# input_output_buffers_DLFO.net
KiCad netlist of a schematic drawn in EAGLE
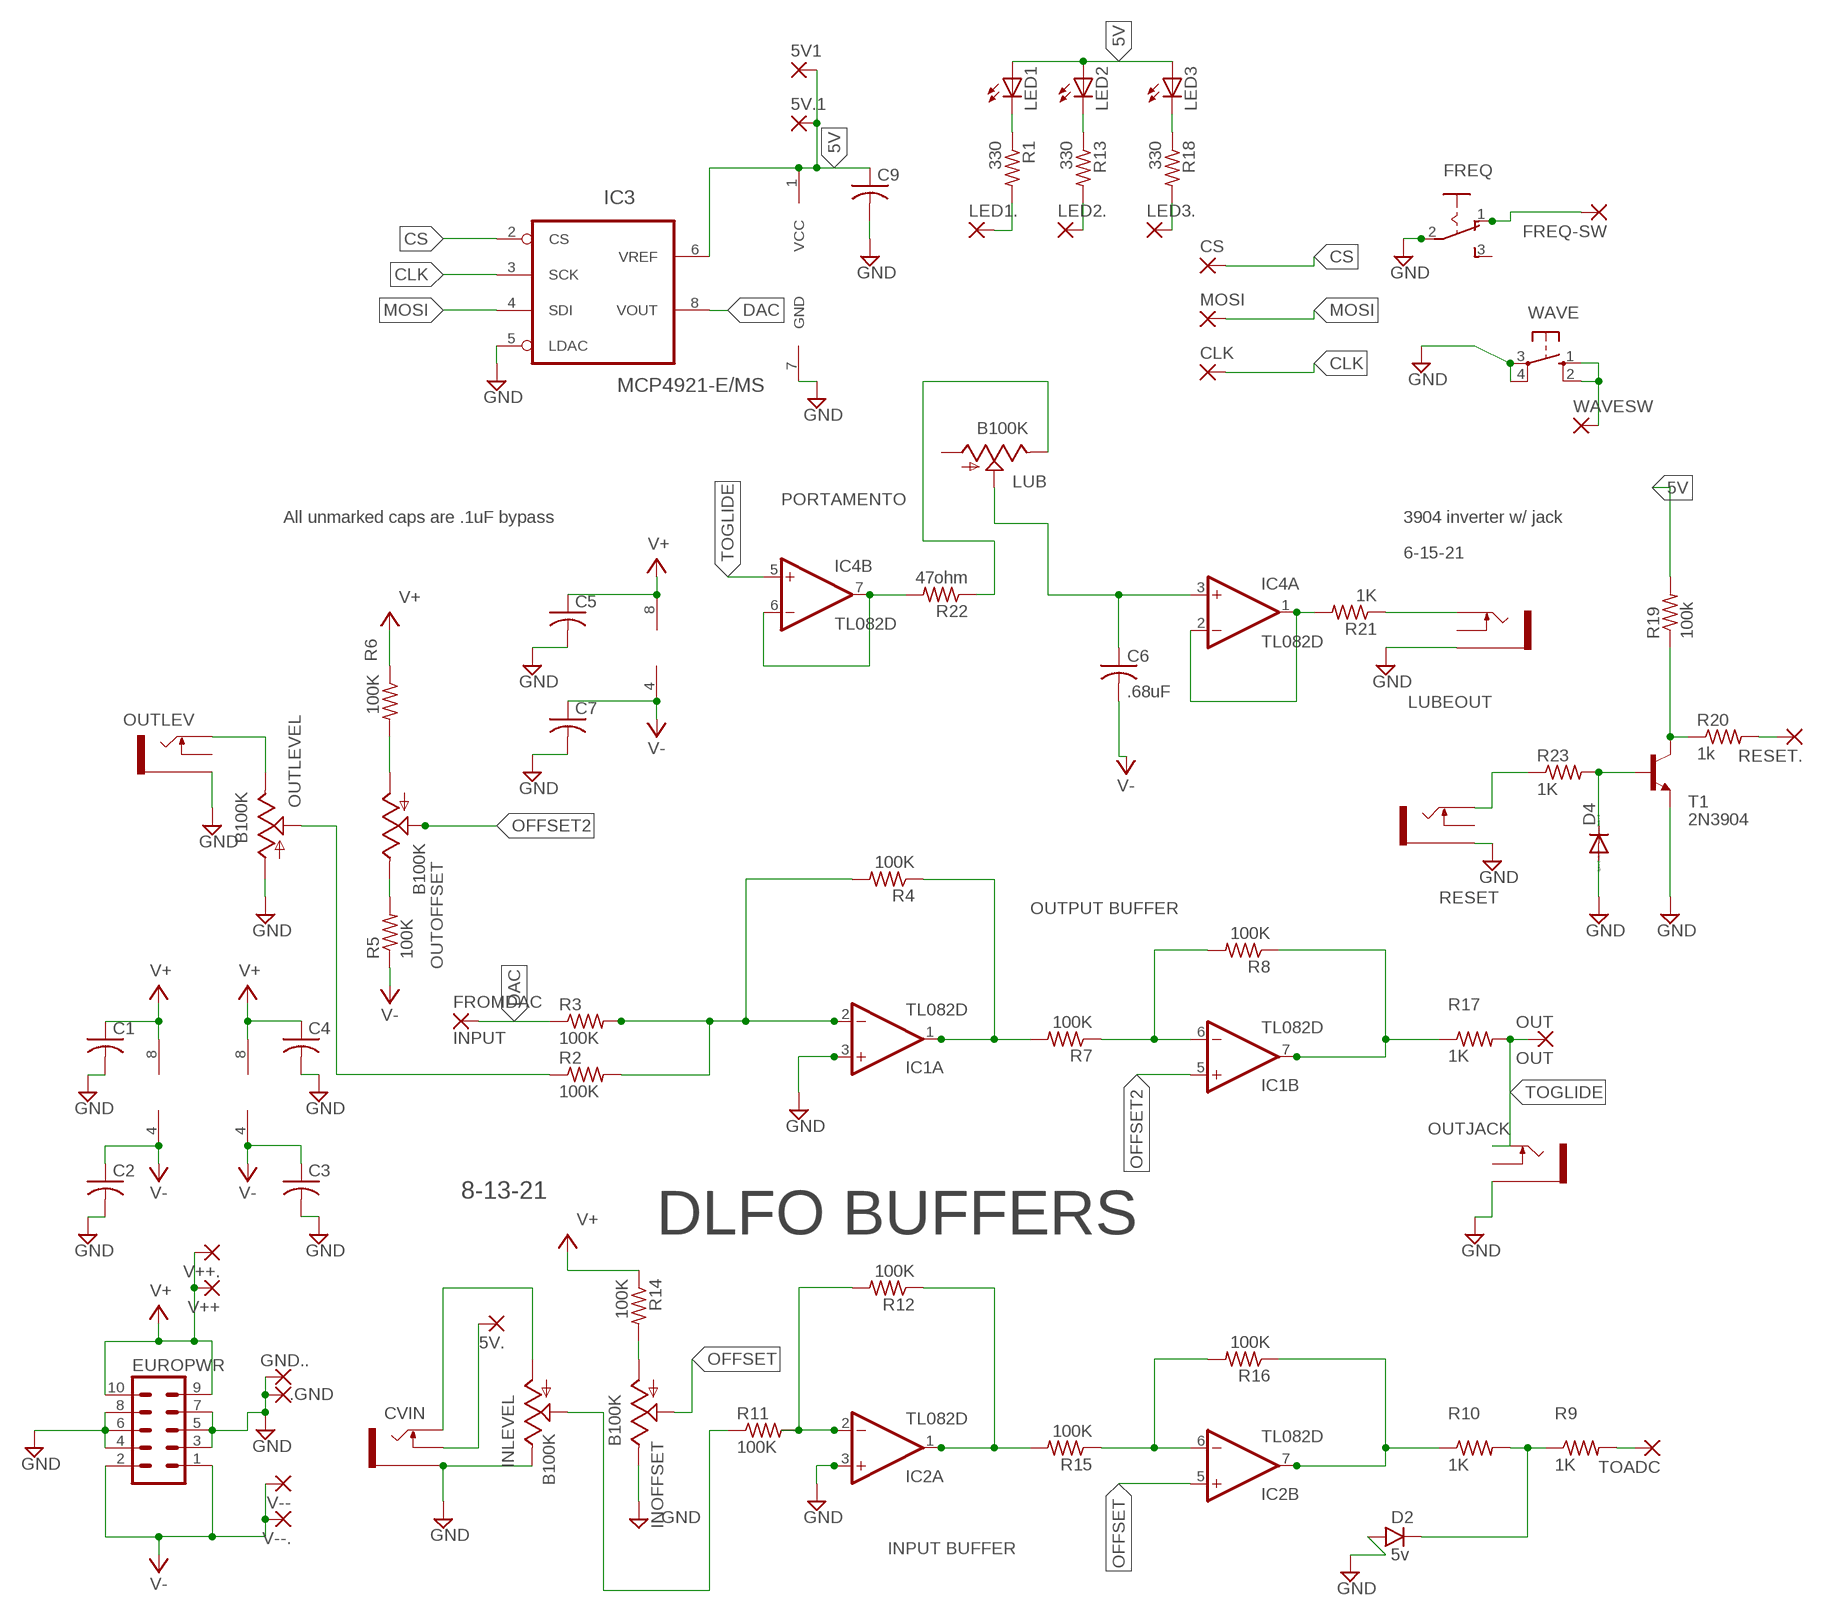
[diagram p0: schematic, sheet 1]

(export (version "E")
  (design (tool "Eeschema 10.0.6"))
  (components
    (comp (ref ".GND")
      (value "3,17/1,3")
      (footprint "eagle-import:3,17_1,3")
      (libsource (lib "eagle-import") (part "3,17/1,3"))
    )
    (comp (ref "5V.")
      (value "3,17/1,3")
      (footprint "eagle-import:3,17_1,3")
      (libsource (lib "eagle-import") (part "3,17/1,3"))
    )
    (comp (ref "5V.1")
      (value "WIREPAD2,54/1,0")
      (footprint "eagle-import:2,54_1,0")
      (libsource (lib "eagle-import") (part "WIREPAD2,54/1,0"))
    )
    (comp (ref "5V1")
      (value "WIREPAD2,54/1,0")
      (footprint "eagle-import:2,54_1,0")
      (libsource (lib "eagle-import") (part "WIREPAD2,54/1,0"))
    )
    (comp (ref "C1")
      (value "C-USC0603")
      (footprint "eagle-import:C0603")
      (libsource (lib "eagle-import") (part "C-USC0603"))
    )
    (comp (ref "C2")
      (value "C-USC0603")
      (footprint "eagle-import:C0603")
      (libsource (lib "eagle-import") (part "C-USC0603"))
    )
    (comp (ref "C3")
      (value "C-USC0603")
      (footprint "eagle-import:C0603")
      (libsource (lib "eagle-import") (part "C-USC0603"))
    )
    (comp (ref "C4")
      (value "C-USC0603")
      (footprint "eagle-import:C0603")
      (libsource (lib "eagle-import") (part "C-USC0603"))
    )
    (comp (ref "C5")
      (value "C-USC0603")
      (footprint "eagle-import:C0603")
      (libsource (lib "eagle-import") (part "C-USC0603"))
    )
    (comp (ref "C6")
      (value ".68uF")
      (footprint "eagle-import:C050-024X044")
      (libsource (lib "eagle-import") (part "C-US050-024X044"))
    )
    (comp (ref "C7")
      (value "C-USC0603")
      (footprint "eagle-import:C0603")
      (libsource (lib "eagle-import") (part "C-USC0603"))
    )
    (comp (ref "C9")
      (value "C-USC0603")
      (footprint "eagle-import:C0603")
      (libsource (lib "eagle-import") (part "C-USC0603"))
    )
    (comp (ref "CLK")
      (value "WIREPAD2,54/1,1")
      (footprint "eagle-import:2,54_1,1")
      (libsource (lib "eagle-import") (part "WIREPAD2,54/1,1"))
    )
    (comp (ref "CS")
      (value "WIREPAD2,54/1,0")
      (footprint "eagle-import:2,54_1,0")
      (libsource (lib "eagle-import") (part "WIREPAD2,54/1,0"))
    )
    (comp (ref "CVIN")
      (value "THONKICONNNEW")
      (footprint "eagle-import:WQP-PJ301M-12_JACK")
      (libsource (lib "eagle-import") (part "THONKICONNNEW"))
    )
    (comp (ref "D2")
      (value "5v")
      (footprint "eagle-import:DO41-2")
      (libsource (lib "eagle-import") (part "DO41.2"))
    )
    (comp (ref "D4")
      (value "1N4148DO35-10")
      (footprint "eagle-import:DO35-10")
      (libsource (lib "eagle-import") (part "1N4148DO35-10"))
    )
    (comp (ref "EUROPWR")
      (value "EURO_POWER_HEADERREGULAR")
      (footprint "eagle-import:EURO_POWER_HEADER")
      (libsource (lib "eagle-import") (part "EURO_POWER_HEADERREGULAR"))
    )
    (comp (ref "FREQ")
      (value "M251")
      (footprint "eagle-import:M251")
      (libsource (lib "eagle-import") (part "M251"))
    )
    (comp (ref "FREQ-SW")
      (value "WIREPAD2,54/0,9")
      (footprint "eagle-import:2,54_0,9")
      (libsource (lib "eagle-import") (part "WIREPAD2,54/0,9"))
    )
    (comp (ref "FROMDAC")
      (value "INPUT")
      (footprint "eagle-import:3,17_1,3")
      (libsource (lib "eagle-import") (part "3,17/1,3"))
    )
    (comp (ref "GND..")
      (value "3,17/1,3")
      (footprint "eagle-import:3,17_1,3")
      (libsource (lib "eagle-import") (part "3,17/1,3"))
    )
    (comp (ref "IC1")
      (value "TL082D")
      (footprint "eagle-import:SO08")
      (libsource (lib "eagle-import") (part "TL082D"))
    )
    (comp (ref "IC2")
      (value "TL082D")
      (footprint "eagle-import:SO08")
      (libsource (lib "eagle-import") (part "TL082D"))
    )
    (comp (ref "IC3")
      (value "MCP4921-E/MS")
      (footprint "eagle-import:MSOP-8")
      (libsource (lib "eagle-import") (part "MCP491-E/MS2"))
    )
    (comp (ref "IC4")
      (value "TL082D")
      (footprint "eagle-import:SO08")
      (libsource (lib "eagle-import") (part "linear_262_TL082D"))
    )
    (comp (ref "INLEVEL")
      (value "B100K")
      (footprint "eagle-import:9MM_SNAP-IN_POT")
      (libsource (lib "eagle-import") (part "9MM_SNAP-IN_POT_"))
    )
    (comp (ref "INOFFSET")
      (value "B100K")
      (footprint "eagle-import:9MM_SNAP-IN_POT")
      (libsource (lib "eagle-import") (part "9MM_SNAP-IN_POT_"))
    )
    (comp (ref "LED1")
      (value "LED3MM")
      (footprint "eagle-import:LED3MM")
      (libsource (lib "eagle-import") (part "LED3MM"))
    )
    (comp (ref "LED1.")
      (value "WIREPAD2,54/1,0")
      (footprint "eagle-import:2,54_1,0")
      (libsource (lib "eagle-import") (part "WIREPAD2,54/1,0"))
    )
    (comp (ref "LED2")
      (value "LED3MM")
      (footprint "eagle-import:LED3MM")
      (libsource (lib "eagle-import") (part "LED3MM"))
    )
    (comp (ref "LED2.")
      (value "WIREPAD2,54/1,0")
      (footprint "eagle-import:2,54_1,0")
      (libsource (lib "eagle-import") (part "WIREPAD2,54/1,0"))
    )
    (comp (ref "LED3")
      (value "LED3MM")
      (footprint "eagle-import:LED3MM")
      (libsource (lib "eagle-import") (part "LED3MM"))
    )
    (comp (ref "LED3.")
      (value "WIREPAD2,54/1,1")
      (footprint "eagle-import:2,54_1,1")
      (libsource (lib "eagle-import") (part "WIREPAD2,54/1,1"))
    )
    (comp (ref "LUB")
      (value "B100K")
      (footprint "eagle-import:9MM_SNAP-IN_POT")
      (libsource (lib "eagle-import") (part "9MM_SNAP-IN_POT_"))
    )
    (comp (ref "LUBEOUT")
      (value "THONKICONNNEW")
      (footprint "eagle-import:WQP-PJ301M-12_JACK")
      (libsource (lib "eagle-import") (part "THONKICONNNEW"))
    )
    (comp (ref "MOSI")
      (value "WIREPAD2,54/1,0")
      (footprint "eagle-import:2,54_1,0")
      (libsource (lib "eagle-import") (part "WIREPAD2,54/1,0"))
    )
    (comp (ref "OUT")
      (value "OUT")
      (footprint "eagle-import:3,17_1,3")
      (libsource (lib "eagle-import") (part "3,17/1,3"))
    )
    (comp (ref "OUTJACK")
      (value "THONKICONNNEW")
      (footprint "eagle-import:WQP-PJ301M-12_JACK")
      (libsource (lib "eagle-import") (part "THONKICONNNEW"))
    )
    (comp (ref "OUTLEV")
      (value "THONKICONNNEW")
      (footprint "eagle-import:WQP-PJ301M-12_JACK")
      (libsource (lib "eagle-import") (part "THONKICONNNEW"))
    )
    (comp (ref "OUTLEVEL")
      (value "B100K")
      (footprint "eagle-import:9MM_SNAP-IN_POT")
      (libsource (lib "eagle-import") (part "9MM_SNAP-IN_POT_"))
    )
    (comp (ref "OUTOFFSET")
      (value "B100K")
      (footprint "eagle-import:9MM_SNAP-IN_POT")
      (libsource (lib "eagle-import") (part "9MM_SNAP-IN_POT_"))
    )
    (comp (ref "R1")
      (value "330")
      (footprint "eagle-import:R0603")
      (libsource (lib "eagle-import") (part "R-US_R0603"))
    )
    (comp (ref "R2")
      (value "100K")
      (footprint "eagle-import:R0603")
      (libsource (lib "eagle-import") (part "R-US_R0603"))
    )
    (comp (ref "R3")
      (value "100K")
      (footprint "eagle-import:R0603")
      (libsource (lib "eagle-import") (part "R-US_R0603"))
    )
    (comp (ref "R4")
      (value "100K")
      (footprint "eagle-import:R0603")
      (libsource (lib "eagle-import") (part "R-US_R0603"))
    )
    (comp (ref "R5")
      (value "100K")
      (footprint "eagle-import:R0603")
      (libsource (lib "eagle-import") (part "R-US_R0603"))
    )
    (comp (ref "R6")
      (value "100K")
      (footprint "eagle-import:R0603")
      (libsource (lib "eagle-import") (part "R-US_R0603"))
    )
    (comp (ref "R7")
      (value "100K")
      (footprint "eagle-import:R0603")
      (libsource (lib "eagle-import") (part "R-US_R0603"))
    )
    (comp (ref "R8")
      (value "100K")
      (footprint "eagle-import:R0603")
      (libsource (lib "eagle-import") (part "R-US_R0603"))
    )
    (comp (ref "R9")
      (value "1K")
      (footprint "eagle-import:R0603")
      (libsource (lib "eagle-import") (part "R-US_R0603"))
    )
    (comp (ref "R10")
      (value "1K")
      (footprint "eagle-import:R0603")
      (libsource (lib "eagle-import") (part "R-US_R0603"))
    )
    (comp (ref "R11")
      (value "100K")
      (footprint "eagle-import:R0603")
      (libsource (lib "eagle-import") (part "R-US_R0603"))
    )
    (comp (ref "R12")
      (value "100K")
      (footprint "eagle-import:R0603")
      (libsource (lib "eagle-import") (part "R-US_R0603"))
    )
    (comp (ref "R13")
      (value "330")
      (footprint "eagle-import:R0603")
      (libsource (lib "eagle-import") (part "R-US_R0603"))
    )
    (comp (ref "R14")
      (value "100K")
      (footprint "eagle-import:R0603")
      (libsource (lib "eagle-import") (part "R-US_R0603"))
    )
    (comp (ref "R15")
      (value "100K")
      (footprint "eagle-import:R0603")
      (libsource (lib "eagle-import") (part "R-US_R0603"))
    )
    (comp (ref "R16")
      (value "100K")
      (footprint "eagle-import:R0603")
      (libsource (lib "eagle-import") (part "R-US_R0603"))
    )
    (comp (ref "R17")
      (value "1K")
      (footprint "eagle-import:R0603")
      (libsource (lib "eagle-import") (part "R-US_R0603"))
    )
    (comp (ref "R18")
      (value "330")
      (footprint "eagle-import:R0603")
      (libsource (lib "eagle-import") (part "R-US_R0603"))
    )
    (comp (ref "R19")
      (value "100k")
      (footprint "eagle-import:R0603")
      (libsource (lib "eagle-import") (part "R-US_R0603"))
    )
    (comp (ref "R20")
      (value "1k")
      (footprint "eagle-import:R0603")
      (libsource (lib "eagle-import") (part "R-US_R0603"))
    )
    (comp (ref "R21")
      (value "1K")
      (footprint "eagle-import:R0603")
      (libsource (lib "eagle-import") (part "R-US_R0603"))
    )
    (comp (ref "R22")
      (value "47ohm")
      (footprint "eagle-import:R0603")
      (libsource (lib "eagle-import") (part "R-US_R0603"))
    )
    (comp (ref "R23")
      (value "1K")
      (footprint "eagle-import:R0603")
      (libsource (lib "eagle-import") (part "R-US_R0603"))
    )
    (comp (ref "RESET")
      (value "THONKICONNNEW")
      (footprint "eagle-import:WQP-PJ301M-12_JACK")
      (libsource (lib "eagle-import") (part "THONKICONNNEW"))
    )
    (comp (ref "RESET.")
      (value "3,17/1,3")
      (footprint "eagle-import:3,17_1,3")
      (libsource (lib "eagle-import") (part "3,17/1,3"))
    )
    (comp (ref "T1")
      (value "2N3904")
      (footprint "eagle-import:TO92")
      (libsource (lib "eagle-import") (part "2N3904"))
    )
    (comp (ref "TOADC")
      (value "3,17/1,3")
      (footprint "eagle-import:3,17_1,3")
      (libsource (lib "eagle-import") (part "3,17/1,3"))
    )
    (comp (ref "V++")
      (value "3,17/1,3")
      (footprint "eagle-import:3,17_1,3")
      (libsource (lib "eagle-import") (part "3,17/1,3"))
    )
    (comp (ref "V++.")
      (value "3,17/1,3")
      (footprint "eagle-import:3,17_1,3")
      (libsource (lib "eagle-import") (part "3,17/1,3"))
    )
    (comp (ref "V--")
      (value "3,17/1,3")
      (footprint "eagle-import:3,17_1,3")
      (libsource (lib "eagle-import") (part "3,17/1,3"))
    )
    (comp (ref "V--.")
      (value "3,17/1,3")
      (footprint "eagle-import:3,17_1,3")
      (libsource (lib "eagle-import") (part "3,17/1,3"))
    )
    (comp (ref "WAVE")
      (value "10-XX")
      (footprint "eagle-import:B3F-10XX")
      (fields (field (name "MPN") "B3F-1000"))
      (libsource (lib "eagle-import") (part "10-XX"))
    )
    (comp (ref "WAVESW")
      (value "WIREPAD2,54/0,9")
      (footprint "eagle-import:2,54_0,9")
      (libsource (lib "eagle-import") (part "WIREPAD2,54/0,9"))
    )
  )
  (nets
    (net (code "1") (name "5V") (class "Default")
      (node (ref "5V.1") (pin "1") (pinfunction "P_1") (pintype "passive"))
      (node (ref "5V1") (pin "1") (pinfunction "P_1") (pintype "passive"))
      (node (ref "C9") (pin "1") (pinfunction "1_1") (pintype "passive"))
      (node (ref "IC3") (pin "1") (pinfunction "VCC_1") (pintype "power_in"))
      (node (ref "IC3") (pin "6") (pinfunction "VREF_6") (pintype "input"))
      (node (ref "LED1") (pin "A") (pinfunction "A_A") (pintype "passive"))
      (node (ref "LED2") (pin "A") (pinfunction "A_A") (pintype "passive"))
      (node (ref "LED3") (pin "A") (pinfunction "A_A") (pintype "passive"))
      (node (ref "R19") (pin "2") (pinfunction "2_2") (pintype "passive"))
    )
    (net (code "2") (name "CLK") (class "Default")
      (node (ref "CLK") (pin "1") (pinfunction "P_1") (pintype "passive"))
      (node (ref "IC3") (pin "3") (pinfunction "SCK_3") (pintype "input"))
    )
    (net (code "3") (name "CS") (class "Default")
      (node (ref "CS") (pin "1") (pinfunction "P_1") (pintype "passive"))
      (node (ref "IC3") (pin "2") (pinfunction "CS_2") (pintype "input"))
    )
    (net (code "4") (name "DAC") (class "Default")
      (node (ref "FROMDAC") (pin "1") (pinfunction "P_1") (pintype "passive"))
      (node (ref "IC3") (pin "8") (pinfunction "VOUT_8") (pintype "output"))
      (node (ref "R3") (pin "1") (pinfunction "1_1") (pintype "passive"))
    )
    (net (code "5") (name "GND") (class "Default")
      (node (ref ".GND") (pin "1") (pinfunction "P_1") (pintype "passive"))
      (node (ref "C1") (pin "2") (pinfunction "2_2") (pintype "passive"))
      (node (ref "C2") (pin "2") (pinfunction "2_2") (pintype "passive"))
      (node (ref "C3") (pin "2") (pinfunction "2_2") (pintype "passive"))
      (node (ref "C4") (pin "2") (pinfunction "2_2") (pintype "passive"))
      (node (ref "C5") (pin "2") (pinfunction "2_2") (pintype "passive"))
      (node (ref "C7") (pin "2") (pinfunction "2_2") (pintype "passive"))
      (node (ref "C9") (pin "2") (pinfunction "2_2") (pintype "passive"))
      (node (ref "CVIN") (pin "P$3_SLEEVE") (pinfunction "SLEEVE_P$3_SLEEVE") (pintype "passive"))
      (node (ref "D2") (pin "A") (pinfunction "A_A") (pintype "passive"))
      (node (ref "D4") (pin "A") (pinfunction "A_A") (pintype "passive"))
      (node (ref "EUROPWR") (pin "3") (pinfunction "3_3") (pintype "passive"))
      (node (ref "EUROPWR") (pin "4") (pinfunction "4_4") (pintype "passive"))
      (node (ref "EUROPWR") (pin "5") (pinfunction "5_5") (pintype "passive"))
      (node (ref "EUROPWR") (pin "6") (pinfunction "6_6") (pintype "passive"))
      (node (ref "EUROPWR") (pin "7") (pinfunction "7_7") (pintype "passive"))
      (node (ref "EUROPWR") (pin "8") (pinfunction "8_8") (pintype "passive"))
      (node (ref "FREQ") (pin "2") (pinfunction "P_2") (pintype "passive"))
      (node (ref "GND..") (pin "1") (pinfunction "P_1") (pintype "passive"))
      (node (ref "IC1") (pin "3") (pinfunction "+IN_3") (pintype "input"))
      (node (ref "IC2") (pin "3") (pinfunction "+IN_3") (pintype "input"))
      (node (ref "IC3") (pin "5") (pinfunction "LDAC_5") (pintype "input"))
      (node (ref "IC3") (pin "7") (pinfunction "GND_7") (pintype "power_in"))
      (node (ref "INLEVEL") (pin "3") (pinfunction "E_3") (pintype "passive"))
      (node (ref "INOFFSET") (pin "3") (pinfunction "E_3") (pintype "passive"))
      (node (ref "LUBEOUT") (pin "P$3_SLEEVE") (pinfunction "SLEEVE_P$3_SLEEVE") (pintype "passive"))
      (node (ref "OUTJACK") (pin "P$3_SLEEVE") (pinfunction "SLEEVE_P$3_SLEEVE") (pintype "passive"))
      (node (ref "OUTLEV") (pin "P$3_SLEEVE") (pinfunction "SLEEVE_P$3_SLEEVE") (pintype "passive"))
      (node (ref "OUTLEVEL") (pin "1") (pinfunction "A_1") (pintype "passive"))
      (node (ref "RESET") (pin "P$3_SLEEVE") (pinfunction "SLEEVE_P$3_SLEEVE") (pintype "passive"))
      (node (ref "T1") (pin "3") (pinfunction "E_3") (pintype "passive"))
      (node (ref "WAVE") (pin "3") (pinfunction "P_3") (pintype "passive"))
      (node (ref "WAVE") (pin "4") (pinfunction "P1_4") (pintype "passive"))
    )
    (net (code "6") (name "MOSI") (class "Default")
      (node (ref "IC3") (pin "4") (pinfunction "SDI_4") (pintype "input"))
      (node (ref "MOSI") (pin "1") (pinfunction "P_1") (pintype "passive"))
    )
    (net (code "7") (name "Net-(5V.-P)") (class "Default")
      (node (ref "5V.") (pin "1") (pinfunction "P_1") (pintype "passive"))
      (node (ref "CVIN") (pin "P$2_SWITCH") (pinfunction "SWITCH_P$2_SWITCH") (pintype "passive"))
    )
    (net (code "8") (name "Net-(CVIN-TIP)") (class "Default")
      (node (ref "CVIN") (pin "P$1_TIP") (pinfunction "TIP_P$1_TIP") (pintype "passive"))
      (node (ref "INLEVEL") (pin "1") (pinfunction "A_1") (pintype "passive"))
    )
    (net (code "9") (name "Net-(D2-PadC)") (class "Default")
      (node (ref "D2") (pin "C") (pinfunction "C_C") (pintype "passive"))
      (node (ref "R10") (pin "2") (pinfunction "2_2") (pintype "passive"))
      (node (ref "R9") (pin "1") (pinfunction "1_1") (pintype "passive"))
    )
    (net (code "10") (name "Net-(FREQ-O)") (class "Default")
      (node (ref "FREQ") (pin "1") (pinfunction "O_1") (pintype "passive"))
      (node (ref "FREQ-SW") (pin "1") (pinfunction "P_1") (pintype "passive"))
    )
    (net (code "11") (name "Net-(IC1A--IN)") (class "Default")
      (node (ref "IC1") (pin "2") (pinfunction "-IN_2") (pintype "input"))
      (node (ref "R2") (pin "2") (pinfunction "2_2") (pintype "passive"))
      (node (ref "R3") (pin "2") (pinfunction "2_2") (pintype "passive"))
      (node (ref "R4") (pin "2") (pinfunction "2_2") (pintype "passive"))
    )
    (net (code "12") (name "Net-(IC1A-OUT)") (class "Default")
      (node (ref "IC1") (pin "1") (pinfunction "OUT_1") (pintype "output"))
      (node (ref "R4") (pin "1") (pinfunction "1_1") (pintype "passive"))
      (node (ref "R7") (pin "2") (pinfunction "2_2") (pintype "passive"))
    )
    (net (code "13") (name "Net-(IC1B--IN)") (class "Default")
      (node (ref "IC1") (pin "6") (pinfunction "-IN_6") (pintype "input"))
      (node (ref "R7") (pin "1") (pinfunction "1_1") (pintype "passive"))
      (node (ref "R8") (pin "2") (pinfunction "2_2") (pintype "passive"))
    )
    (net (code "14") (name "Net-(IC1B-OUT)") (class "Default")
      (node (ref "IC1") (pin "7") (pinfunction "OUT_7") (pintype "output"))
      (node (ref "R17") (pin "1") (pinfunction "1_1") (pintype "passive"))
      (node (ref "R8") (pin "1") (pinfunction "1_1") (pintype "passive"))
    )
    (net (code "15") (name "Net-(IC2A--IN)") (class "Default")
      (node (ref "IC2") (pin "2") (pinfunction "-IN_2") (pintype "input"))
      (node (ref "R11") (pin "2") (pinfunction "2_2") (pintype "passive"))
      (node (ref "R12") (pin "2") (pinfunction "2_2") (pintype "passive"))
    )
    (net (code "16") (name "Net-(IC2A-OUT)") (class "Default")
      (node (ref "IC2") (pin "1") (pinfunction "OUT_1") (pintype "output"))
      (node (ref "R12") (pin "1") (pinfunction "1_1") (pintype "passive"))
      (node (ref "R15") (pin "2") (pinfunction "2_2") (pintype "passive"))
    )
    (net (code "17") (name "Net-(IC2B--IN)") (class "Default")
      (node (ref "IC2") (pin "6") (pinfunction "-IN_6") (pintype "input"))
      (node (ref "R15") (pin "1") (pinfunction "1_1") (pintype "passive"))
      (node (ref "R16") (pin "2") (pinfunction "2_2") (pintype "passive"))
    )
    (net (code "18") (name "Net-(IC2B-OUT)") (class "Default")
      (node (ref "IC2") (pin "7") (pinfunction "OUT_7") (pintype "output"))
      (node (ref "R10") (pin "1") (pinfunction "1_1") (pintype "passive"))
      (node (ref "R16") (pin "1") (pinfunction "1_1") (pintype "passive"))
    )
    (net (code "19") (name "Net-(IC4A-+IN)") (class "Default")
      (node (ref "C6") (pin "1") (pinfunction "1_1") (pintype "passive"))
      (node (ref "IC4") (pin "3") (pinfunction "+IN_3") (pintype "input"))
      (node (ref "LUB") (pin "2") (pinfunction "S_2") (pintype "passive"))
    )
    (net (code "20") (name "Net-(IC4A--IN)") (class "Default")
      (node (ref "IC4") (pin "1") (pinfunction "OUT_1") (pintype "output"))
      (node (ref "IC4") (pin "2") (pinfunction "-IN_2") (pintype "input"))
      (node (ref "R21") (pin "2") (pinfunction "2_2") (pintype "passive"))
    )
    (net (code "21") (name "Net-(IC4B--IN)") (class "Default")
      (node (ref "IC4") (pin "6") (pinfunction "-IN_6") (pintype "input"))
      (node (ref "IC4") (pin "7") (pinfunction "OUT_7") (pintype "output"))
      (node (ref "R22") (pin "2") (pinfunction "2_2") (pintype "passive"))
    )
    (net (code "22") (name "Net-(INLEVEL-S)") (class "Default")
      (node (ref "INLEVEL") (pin "2") (pinfunction "S_2") (pintype "passive"))
      (node (ref "R11") (pin "1") (pinfunction "1_1") (pintype "passive"))
    )
    (net (code "23") (name "Net-(INOFFSET-A)") (class "Default")
      (node (ref "INOFFSET") (pin "1") (pinfunction "A_1") (pintype "passive"))
      (node (ref "R14") (pin "2") (pinfunction "2_2") (pintype "passive"))
    )
    (net (code "24") (name "Net-(LED1-C)") (class "Default")
      (node (ref "LED1") (pin "K") (pinfunction "C_K") (pintype "passive"))
      (node (ref "R1") (pin "1") (pinfunction "1_1") (pintype "passive"))
    )
    (net (code "25") (name "Net-(LED1.-P)") (class "Default")
      (node (ref "LED1.") (pin "1") (pinfunction "P_1") (pintype "passive"))
      (node (ref "R1") (pin "2") (pinfunction "2_2") (pintype "passive"))
    )
    (net (code "26") (name "Net-(LED2-C)") (class "Default")
      (node (ref "LED2") (pin "K") (pinfunction "C_K") (pintype "passive"))
      (node (ref "R13") (pin "1") (pinfunction "1_1") (pintype "passive"))
    )
    (net (code "27") (name "Net-(LED2.-P)") (class "Default")
      (node (ref "LED2.") (pin "1") (pinfunction "P_1") (pintype "passive"))
      (node (ref "R13") (pin "2") (pinfunction "2_2") (pintype "passive"))
    )
    (net (code "28") (name "Net-(LED3-C)") (class "Default")
      (node (ref "LED3") (pin "K") (pinfunction "C_K") (pintype "passive"))
      (node (ref "R18") (pin "1") (pinfunction "1_1") (pintype "passive"))
    )
    (net (code "29") (name "Net-(LED3.-P)") (class "Default")
      (node (ref "LED3.") (pin "1") (pinfunction "P_1") (pintype "passive"))
      (node (ref "R18") (pin "2") (pinfunction "2_2") (pintype "passive"))
    )
    (net (code "30") (name "Net-(LUB-E)") (class "Default")
      (node (ref "LUB") (pin "3") (pinfunction "E_3") (pintype "passive"))
      (node (ref "R22") (pin "1") (pinfunction "1_1") (pintype "passive"))
    )
    (net (code "31") (name "Net-(LUBEOUT-TIP)") (class "Default")
      (node (ref "LUBEOUT") (pin "P$1_TIP") (pinfunction "TIP_P$1_TIP") (pintype "passive"))
      (node (ref "R21") (pin "1") (pinfunction "1_1") (pintype "passive"))
    )
    (net (code "32") (name "Net-(OUTLEV-TIP)") (class "Default")
      (node (ref "OUTLEV") (pin "P$1_TIP") (pinfunction "TIP_P$1_TIP") (pintype "passive"))
      (node (ref "OUTLEVEL") (pin "3") (pinfunction "E_3") (pintype "passive"))
    )
    (net (code "33") (name "Net-(OUTLEVEL-S)") (class "Default")
      (node (ref "OUTLEVEL") (pin "2") (pinfunction "S_2") (pintype "passive"))
      (node (ref "R2") (pin "1") (pinfunction "1_1") (pintype "passive"))
    )
    (net (code "34") (name "Net-(OUTOFFSET-A)") (class "Default")
      (node (ref "OUTOFFSET") (pin "1") (pinfunction "A_1") (pintype "passive"))
      (node (ref "R6") (pin "2") (pinfunction "2_2") (pintype "passive"))
    )
    (net (code "35") (name "Net-(OUTOFFSET-E)") (class "Default")
      (node (ref "OUTOFFSET") (pin "3") (pinfunction "E_3") (pintype "passive"))
      (node (ref "R5") (pin "2") (pinfunction "2_2") (pintype "passive"))
    )
    (net (code "36") (name "Net-(RESET-TIP)") (class "Default")
      (node (ref "R23") (pin "1") (pinfunction "1_1") (pintype "passive"))
      (node (ref "RESET") (pin "P$1_TIP") (pinfunction "TIP_P$1_TIP") (pintype "passive"))
    )
    (net (code "37") (name "Net-(RESET.-P)") (class "Default")
      (node (ref "R20") (pin "2") (pinfunction "2_2") (pintype "passive"))
      (node (ref "RESET.") (pin "1") (pinfunction "P_1") (pintype "passive"))
    )
    (net (code "38") (name "Net-(T1-B)") (class "Default")
      (node (ref "D4") (pin "C") (pinfunction "C_C") (pintype "passive"))
      (node (ref "R23") (pin "2") (pinfunction "2_2") (pintype "passive"))
      (node (ref "T1") (pin "2") (pinfunction "B_2") (pintype "passive"))
    )
    (net (code "39") (name "Net-(T1-C)") (class "Default")
      (node (ref "R19") (pin "1") (pinfunction "1_1") (pintype "passive"))
      (node (ref "R20") (pin "1") (pinfunction "1_1") (pintype "passive"))
      (node (ref "T1") (pin "1") (pinfunction "C_1") (pintype "passive"))
    )
    (net (code "40") (name "Net-(TOADC-P)") (class "Default")
      (node (ref "R9") (pin "2") (pinfunction "2_2") (pintype "passive"))
      (node (ref "TOADC") (pin "1") (pinfunction "P_1") (pintype "passive"))
    )
    (net (code "41") (name "Net-(WAVE-S)") (class "Default")
      (node (ref "WAVE") (pin "1") (pinfunction "S_1") (pintype "passive"))
      (node (ref "WAVE") (pin "2") (pinfunction "S1_2") (pintype "passive"))
      (node (ref "WAVESW") (pin "1") (pinfunction "P_1") (pintype "passive"))
    )
    (net (code "42") (name "OFFSET") (class "Default")
      (node (ref "IC2") (pin "5") (pinfunction "+IN_5") (pintype "input"))
      (node (ref "INOFFSET") (pin "2") (pinfunction "S_2") (pintype "passive"))
    )
    (net (code "43") (name "OFFSET2") (class "Default")
      (node (ref "IC1") (pin "5") (pinfunction "+IN_5") (pintype "input"))
      (node (ref "OUTOFFSET") (pin "2") (pinfunction "S_2") (pintype "passive"))
    )
    (net (code "44") (name "TOGLIDE") (class "Default")
      (node (ref "IC4") (pin "5") (pinfunction "+IN_5") (pintype "input"))
      (node (ref "OUT") (pin "1") (pinfunction "P_1") (pintype "passive"))
      (node (ref "OUTJACK") (pin "P$1_TIP") (pinfunction "TIP_P$1_TIP") (pintype "passive"))
      (node (ref "R17") (pin "2") (pinfunction "2_2") (pintype "passive"))
    )
    (net (code "45") (name "V+") (class "Default")
      (node (ref "C1") (pin "1") (pinfunction "1_1") (pintype "passive"))
      (node (ref "C4") (pin "1") (pinfunction "1_1") (pintype "passive"))
      (node (ref "C5") (pin "1") (pinfunction "1_1") (pintype "passive"))
      (node (ref "EUROPWR") (pin "10") (pinfunction "10_10") (pintype "passive"))
      (node (ref "EUROPWR") (pin "9") (pinfunction "9_9") (pintype "passive"))
      (node (ref "IC1") (pin "8") (pinfunction "V+_8") (pintype "power_in"))
      (node (ref "IC2") (pin "8") (pinfunction "V+_8") (pintype "power_in"))
      (node (ref "IC4") (pin "8") (pinfunction "V+_8") (pintype "power_in"))
      (node (ref "R14") (pin "1") (pinfunction "1_1") (pintype "passive"))
      (node (ref "R6") (pin "1") (pinfunction "1_1") (pintype "passive"))
      (node (ref "V++") (pin "1") (pinfunction "P_1") (pintype "passive"))
      (node (ref "V++.") (pin "1") (pinfunction "P_1") (pintype "passive"))
    )
    (net (code "46") (name "V-") (class "Default")
      (node (ref "C2") (pin "1") (pinfunction "1_1") (pintype "passive"))
      (node (ref "C3") (pin "1") (pinfunction "1_1") (pintype "passive"))
      (node (ref "C6") (pin "2") (pinfunction "2_2") (pintype "passive"))
      (node (ref "C7") (pin "1") (pinfunction "1_1") (pintype "passive"))
      (node (ref "EUROPWR") (pin "1") (pinfunction "1_1") (pintype "passive"))
      (node (ref "EUROPWR") (pin "2") (pinfunction "2_2") (pintype "passive"))
      (node (ref "IC1") (pin "4") (pinfunction "V-_4") (pintype "power_in"))
      (node (ref "IC2") (pin "4") (pinfunction "V-_4") (pintype "power_in"))
      (node (ref "IC4") (pin "4") (pinfunction "V-_4") (pintype "power_in"))
      (node (ref "R5") (pin "1") (pinfunction "1_1") (pintype "passive"))
      (node (ref "V--") (pin "1") (pinfunction "P_1") (pintype "passive"))
      (node (ref "V--.") (pin "1") (pinfunction "P_1") (pintype "passive"))
    )
    (net (code "47") (name "unconnected-(FREQ-S-Pad3)") (class "Default")
      (node (ref "FREQ") (pin "3") (pinfunction "S_3") (pintype "passive"))
    )
    (net (code "48") (name "unconnected-(LUB-A-Pad1)") (class "Default")
      (node (ref "LUB") (pin "1") (pinfunction "A_1") (pintype "passive"))
    )
    (net (code "49") (name "unconnected-(LUBEOUT-SWITCH-PadP$2_SWITCH)") (class "Default")
      (node (ref "LUBEOUT") (pin "P$2_SWITCH") (pinfunction "SWITCH_P$2_SWITCH") (pintype "passive"))
    )
    (net (code "50") (name "unconnected-(OUTJACK-SWITCH-PadP$2_SWITCH)") (class "Default")
      (node (ref "OUTJACK") (pin "P$2_SWITCH") (pinfunction "SWITCH_P$2_SWITCH") (pintype "passive"))
    )
    (net (code "51") (name "unconnected-(OUTLEV-SWITCH-PadP$2_SWITCH)") (class "Default")
      (node (ref "OUTLEV") (pin "P$2_SWITCH") (pinfunction "SWITCH_P$2_SWITCH") (pintype "passive"))
    )
    (net (code "52") (name "unconnected-(RESET-SWITCH-PadP$2_SWITCH)") (class "Default")
      (node (ref "RESET") (pin "P$2_SWITCH") (pinfunction "SWITCH_P$2_SWITCH") (pintype "passive"))
    )
  )
)
